# 60-hv-amp-dewhitening.net
KiCad netlist of a schematic drawn in EAGLE
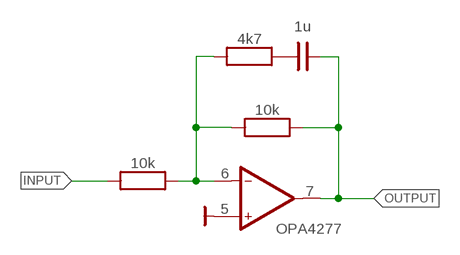
[diagram p0: schematic, sheet 1]

(export (version "E")
  (design (tool "Eeschema 10.0.6"))
  (components
    (comp (ref "C5")
      (value "1u")
      (footprint "eagle-import:C02-MKS2-5.0-N")
      (libsource (lib "eagle-import") (part "C02-MKS2-5.0-N"))
    )
    (comp (ref "N1")
      (value "OPA4277")
      (footprint "eagle-import:DIP14L")
      (libsource (lib "eagle-import") (part "OPA4277L"))
    )
    (comp (ref "R17")
      (value "10k")
      (footprint "eagle-import:R04N")
      (libsource (lib "eagle-import") (part "RN"))
    )
    (comp (ref "R21")
      (value "4k7")
      (footprint "eagle-import:R04N")
      (libsource (lib "eagle-import") (part "RN"))
    )
    (comp (ref "R25")
      (value "10k")
      (footprint "eagle-import:R04N")
      (libsource (lib "eagle-import") (part "RN"))
    )
  )
  (nets
    (net (code "1") (name "INPUT") (class "Default")
      (node (ref "R17") (pin "1") (pinfunction "1_1") (pintype "passive"))
    )
    (net (code "2") (name "Net-(C5-Pad1)") (class "Default")
      (node (ref "C5") (pin "1") (pinfunction "1_1") (pintype "passive"))
      (node (ref "R21") (pin "2") (pinfunction "2_2") (pintype "passive"))
    )
    (net (code "3") (name "Net-(N1B-IN-)") (class "Default")
      (node (ref "N1") (pin "6") (pinfunction "IN-_6") (pintype "input"))
      (node (ref "R17") (pin "2") (pinfunction "2_2") (pintype "passive"))
      (node (ref "R21") (pin "1") (pinfunction "1_1") (pintype "passive"))
      (node (ref "R25") (pin "1") (pinfunction "1_1") (pintype "passive"))
    )
    (net (code "4") (name "OUTPUT") (class "Default")
      (node (ref "C5") (pin "2") (pinfunction "2_2") (pintype "passive"))
      (node (ref "N1") (pin "7") (pinfunction "OUT_7") (pintype "output"))
      (node (ref "R25") (pin "2") (pinfunction "2_2") (pintype "passive"))
    )
    (net (code "5") (name "VG") (class "Default")
      (node (ref "N1") (pin "5") (pinfunction "IN+_5") (pintype "input"))
    )
  )
)
